# schematic_drive_2024-08-23.net
KiCad netlist of a schematic drawn in Altium Designer
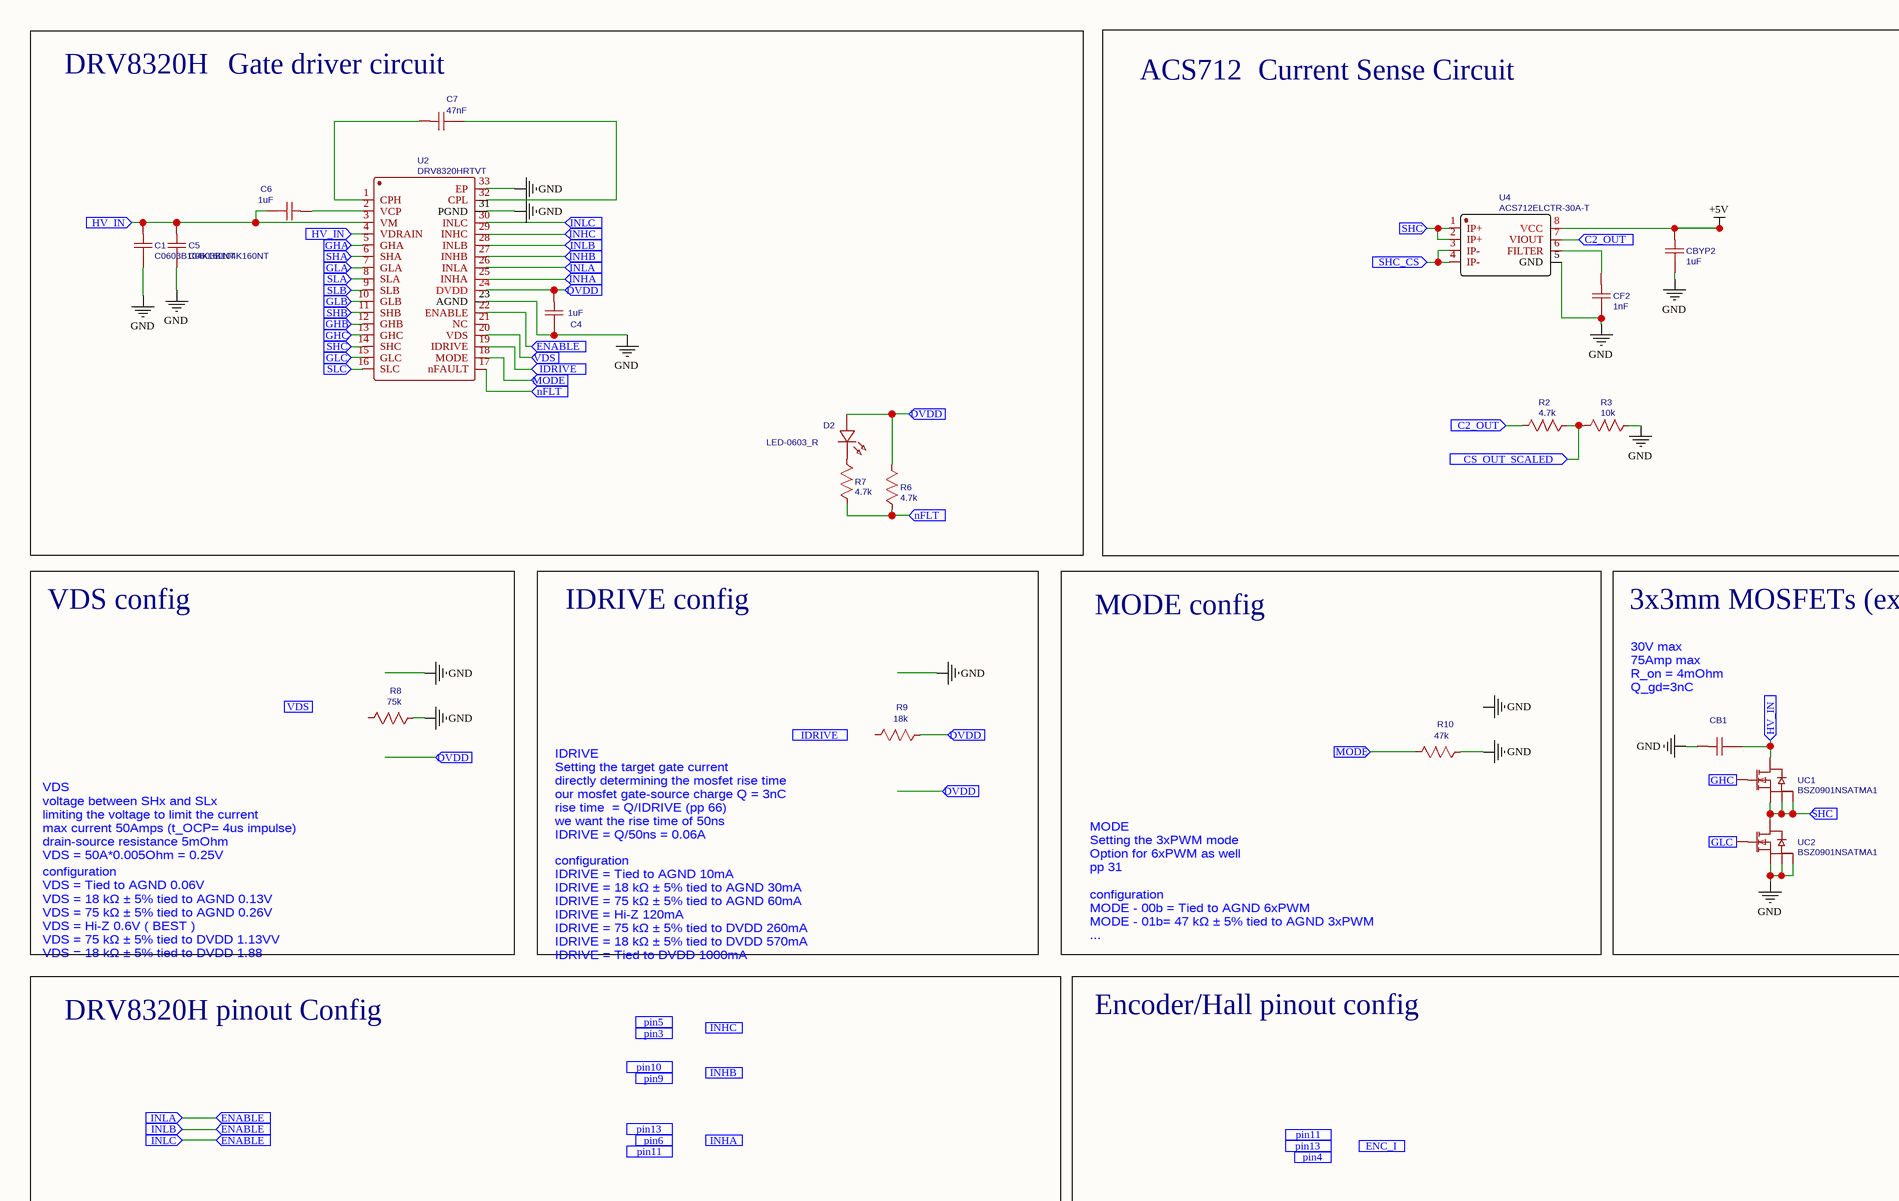
[diagram p0: schematic_drive_2024-08-23.schdoc, top left]
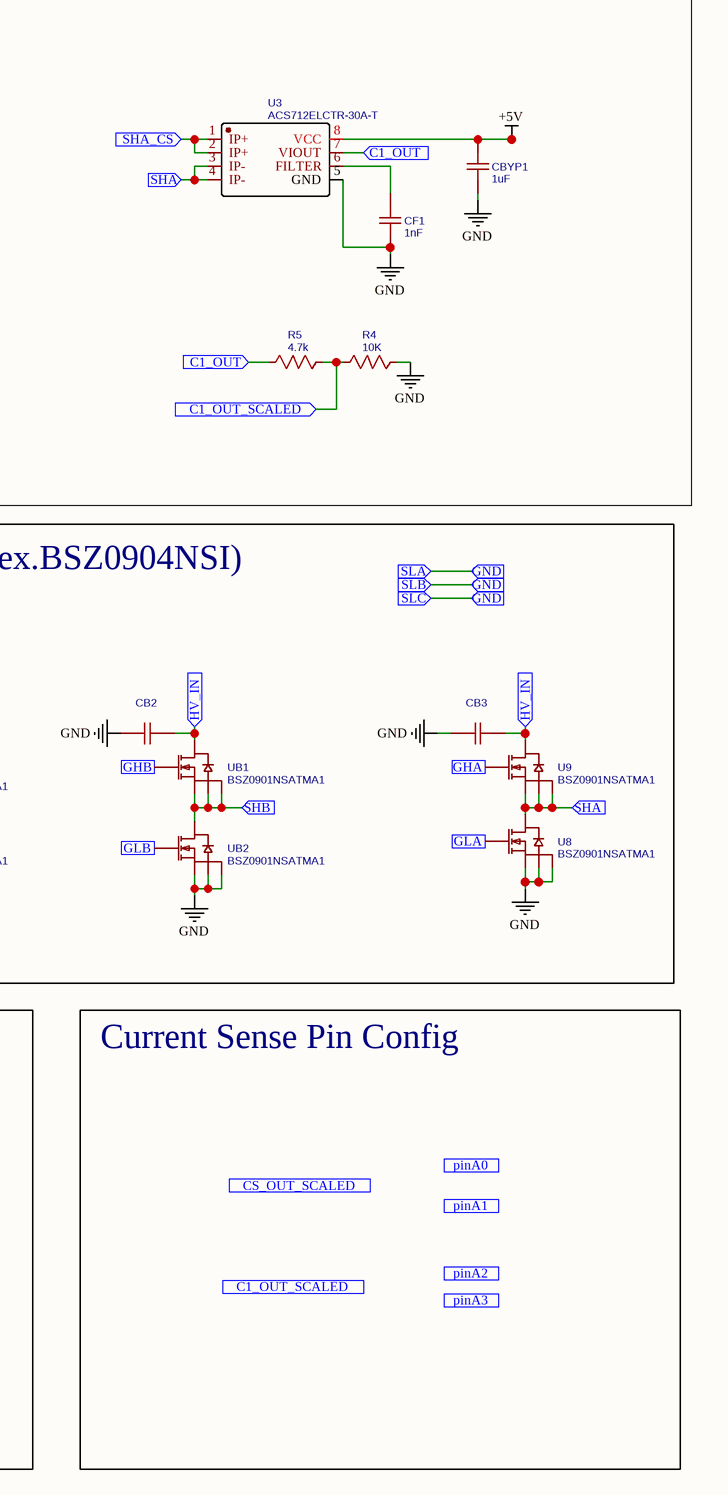
[diagram p1: schematic_drive_2024-08-23.schdoc, top right]
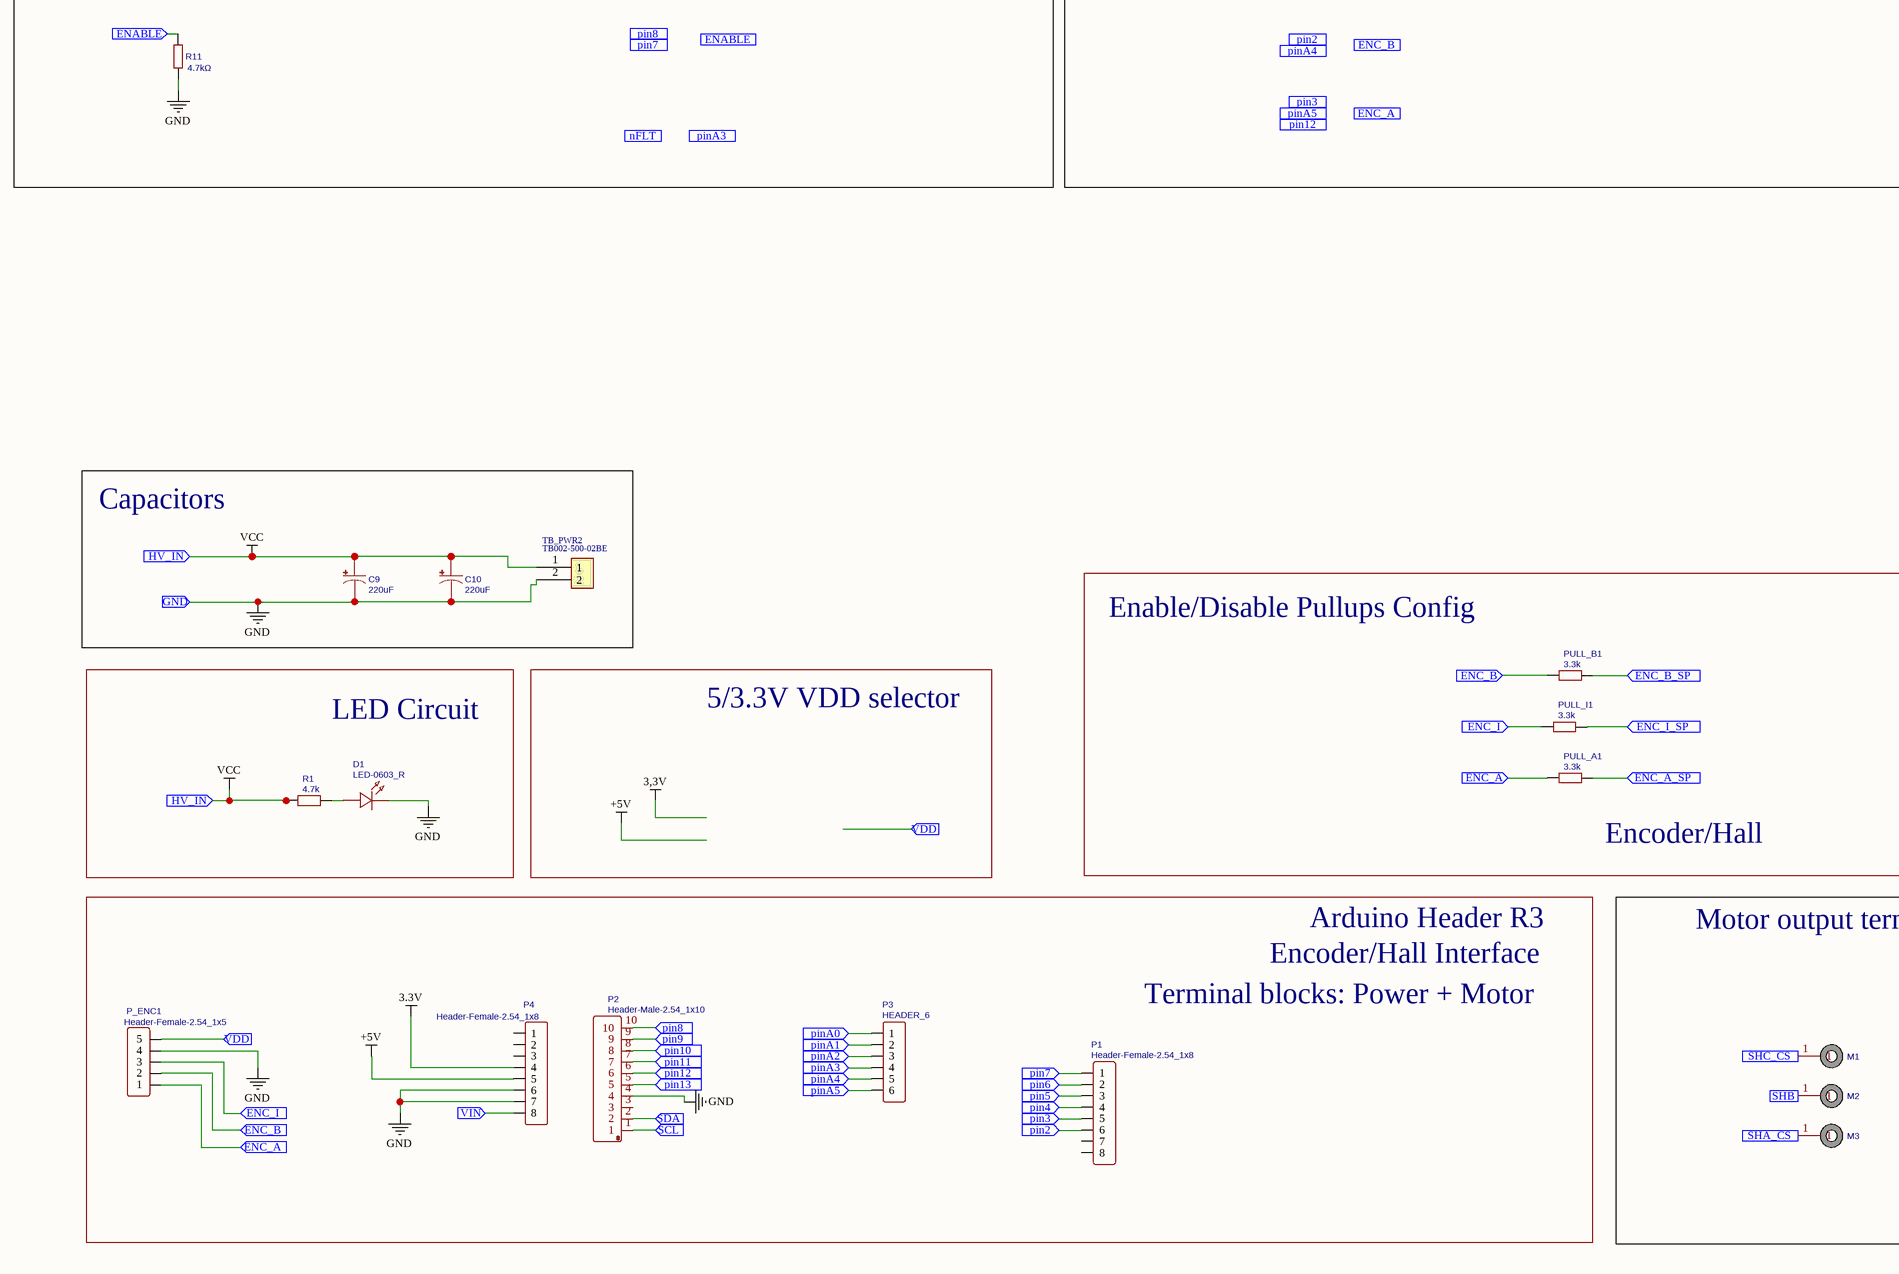
[diagram p2: schematic_drive_2024-08-23.schdoc, bottom left]
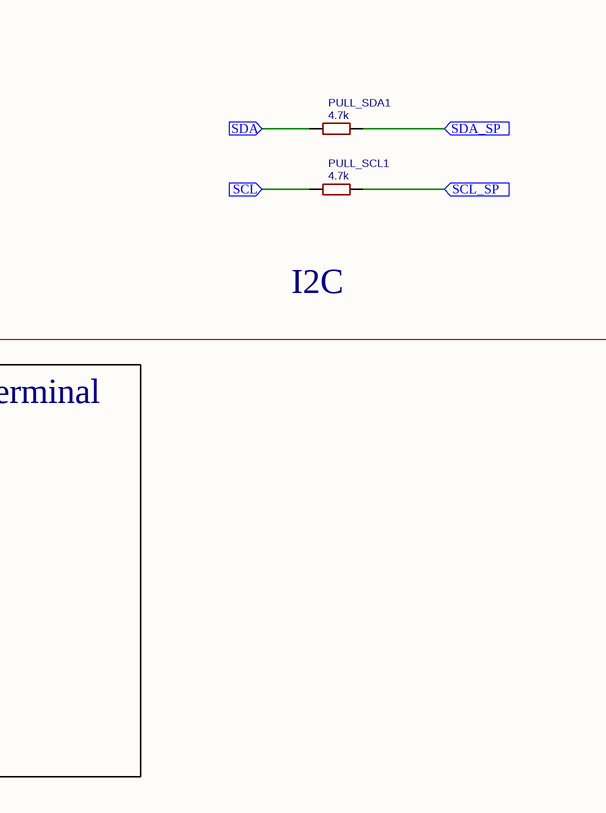
[diagram p3: schematic_drive_2024-08-23.schdoc, bottom right]

(export (version "E")
  (design (tool "Eeschema 10.0.6"))
  (components
    (comp (ref "C1")
      (value "C0603B104K160NT")
      (fields (field (name "MANUFACTURER") "TORCH(火炬)") (field (name "CONTRIBUTOR") "lcsc"))
      (libsource (lib "altium-import") (part "root_1_C0603B104K160NT_"))
    )
    (comp (ref "C4")
      (value "1uF")
      (fields (field (name "CONTRIBUTOR") "LCEDA_Lib"))
      (libsource (lib "altium-import") (part "root_1_1uF_"))
    )
    (comp (ref "C5")
      (value "C0603B104K160NT")
      (fields (field (name "MANUFACTURER") "TORCH(火炬)") (field (name "CONTRIBUTOR") "lcsc"))
      (libsource (lib "altium-import") (part "root_1_C0603B104K160NT_"))
    )
    (comp (ref "C6")
      (value "1uF")
      (fields (field (name "CONTRIBUTOR") "LCEDA_Lib"))
      (libsource (lib "altium-import") (part "root_0_1uF_"))
    )
    (comp (ref "C7")
      (value "47nF")
      (fields (field (name "CONTRIBUTOR") "LCEDA_Lib"))
      (libsource (lib "altium-import") (part "root_2_47nF_"))
    )
    (comp (ref "C9")
      (value "220uF")
      (fields
        (field (name "MANUFACTURER") "VT(首科)")
        (field (name "MANUFACTURER PART") "VT1V221M-CRF10")
        (field (name "CONTRIBUTOR") "LCSC")
      )
      (libsource (lib "altium-import") (part "root_0_220uF_"))
    )
    (comp (ref "C10")
      (value "220uF")
      (fields
        (field (name "MANUFACTURER") "VT(首科)")
        (field (name "MANUFACTURER PART") "VT1V221M-CRF10")
        (field (name "CONTRIBUTOR") "LCSC")
      )
      (libsource (lib "altium-import") (part "root_0_220uF_"))
    )
    (comp (ref "CB1")
      (value "C0603B104K160NT")
      (fields (field (name "MANUFACTURER") "TORCH(火炬)") (field (name "CONTRIBUTOR") "lcsc"))
      (libsource (lib "altium-import") (part "root_2_C0603B104K160NT_"))
    )
    (comp (ref "CB2")
      (value "C0603B104K160NT")
      (fields (field (name "MANUFACTURER") "TORCH(火炬)") (field (name "CONTRIBUTOR") "lcsc"))
      (libsource (lib "altium-import") (part "root_0_C0603B104K160NT_"))
    )
    (comp (ref "CB3")
      (value "C0603B104K160NT")
      (fields (field (name "MANUFACTURER") "TORCH(火炬)") (field (name "CONTRIBUTOR") "lcsc"))
      (libsource (lib "altium-import") (part "root_2_C0603B104K160NT_"))
    )
    (comp (ref "CBYP1")
      (value "1uF")
      (fields (field (name "CONTRIBUTOR") "LCEDA_Lib"))
      (libsource (lib "altium-import") (part "root_1_1uF_"))
    )
    (comp (ref "CBYP2")
      (value "1uF")
      (fields (field (name "CONTRIBUTOR") "LCEDA_Lib"))
      (libsource (lib "altium-import") (part "root_1_1uF_"))
    )
    (comp (ref "CF1")
      (value "1nF")
      (fields (field (name "CONTRIBUTOR") "LCEDA_Lib"))
      (libsource (lib "altium-import") (part "root_1_1nF_"))
    )
    (comp (ref "CF2")
      (value "1nF")
      (fields (field (name "CONTRIBUTOR") "LCEDA_Lib"))
      (libsource (lib "altium-import") (part "root_1_1nF_"))
    )
    (comp (ref "D1")
      (value "LED-0603_R")
      (fields
        (field (name "MANUFACTURER") "EVERLIGHT(台湾亿光)")
        (field (name "MANUFACTURER PART") "19-217/R6C-AL1M2VY/3T")
        (field (name "CONTRIBUTOR") "LCEDA_01")
      )
      (libsource (lib "altium-import") (part "root_0_LED-0603_R_"))
    )
    (comp (ref "D2")
      (value "LED-0603_R")
      (fields
        (field (name "MANUFACTURER") "EVERLIGHT(台湾亿光)")
        (field (name "MANUFACTURER PART") "19-217/R6C-AL1M2VY/3T")
        (field (name "CONTRIBUTOR") "LCEDA_01")
      )
      (libsource (lib "altium-import") (part "root_3_LED-0603_R_"))
    )
    (comp (ref "M1")
      (value "M2 PLATED HOLE WITH MINI HOLES")
      (fields (field (name "CONTRIBUTOR") "Andrew Young"))
      (libsource (lib "altium-import") (part "root_0_M2 PLATED HOLE WITH MINI HOLES_"))
    )
    (comp (ref "M2")
      (value "M2 PLATED HOLE WITH MINI HOLES")
      (fields (field (name "CONTRIBUTOR") "Andrew Young"))
      (libsource (lib "altium-import") (part "root_0_M2 PLATED HOLE WITH MINI HOLES_"))
    )
    (comp (ref "M3")
      (value "M2 PLATED HOLE WITH MINI HOLES")
      (fields (field (name "CONTRIBUTOR") "Andrew Young"))
      (libsource (lib "altium-import") (part "root_0_M2 PLATED HOLE WITH MINI HOLES_"))
    )
    (comp (ref "P1")
      (value "Header-Female-2.54_1x8")
      (fields
        (field (name "MANUFACTURER") "BOOMELE")
        (field (name "MANUFACTURER PART") "Female headerHDR1X8-2.54")
      )
      (libsource (lib "altium-import") (part "root_0_Header-Female-2.54_1x8_"))
    )
    (comp (ref "P2")
      (value "Header-Male-2.54_1x10")
      (fields (field (name "MANUFACTURER PART") "Headers  Pins2.54mm1*10P"))
      (libsource (lib "altium-import") (part "root_2_Header-Male-2.54_1x10_"))
    )
    (comp (ref "P3") (value "HEADER_6") (libsource (lib "altium-import") (part "root_0_HEADER_6_")))
    (comp (ref "P4")
      (value "Header-Female-2.54_1x8")
      (fields
        (field (name "MANUFACTURER") "BOOMELE")
        (field (name "MANUFACTURER PART") "Female headerHDR1X8-2.54")
      )
      (libsource (lib "altium-import") (part "root_0_Header-Female-2.54_1x8_"))
    )
    (comp (ref "PULL_A1") (value "3.3k") (libsource (lib "altium-import") (part "root_2_3.3k_")))
    (comp (ref "PULL_B1") (value "3.3k") (libsource (lib "altium-import") (part "root_2_3.3k_")))
    (comp (ref "PULL_I1") (value "3.3k") (libsource (lib "altium-import") (part "root_2_3.3k_")))
    (comp (ref "PULL_SCL1")
      (value "4.7k")
      (fields (field (name "MANUFACTURER") "UniOhm") (field (name "MANUFACTURER PART") "0603WAF4701T5E"))
      (libsource (lib "altium-import") (part "root_2_4.7k_"))
    )
    (comp (ref "PULL_SDA1")
      (value "4.7k")
      (fields (field (name "MANUFACTURER") "UniOhm") (field (name "MANUFACTURER PART") "0603WAF4701T5E"))
      (libsource (lib "altium-import") (part "root_2_4.7k_"))
    )
    (comp (ref "P_ENC1")
      (value "Header-Female-2.54_1x5")
      (fields
        (field (name "MANUFACTURER") "BOOMELE")
        (field (name "MANUFACTURER PART") "2.54mm 1*5p Female header")
      )
      (libsource (lib "altium-import") (part "root_2_Header-Female-2.54_1x5_"))
    )
    (comp (ref "R1")
      (value "4.7k")
      (fields (field (name "MANUFACTURER") "UniOhm") (field (name "MANUFACTURER PART") "0603WAF4701T5E"))
      (libsource (lib "altium-import") (part "root_2_4.7k_"))
    )
    (comp (ref "R2")
      (value "4.7k")
      (fields (field (name "CONTRIBUTOR") "LCEDA_Lib"))
      (libsource (lib "altium-import") (part "root_0_4.7k_"))
    )
    (comp (ref "R3")
      (value "10k")
      (fields (field (name "CONTRIBUTOR") "LCEDA_Lib"))
      (libsource (lib "altium-import") (part "root_0_10k_"))
    )
    (comp (ref "R4")
      (value "10K")
      (fields (field (name "CONTRIBUTOR") "LCEDA_Lib"))
      (libsource (lib "altium-import") (part "root_0_10K_"))
    )
    (comp (ref "R5")
      (value "4.7k")
      (fields (field (name "CONTRIBUTOR") "LCEDA_Lib"))
      (libsource (lib "altium-import") (part "root_0_4.7k_"))
    )
    (comp (ref "R6")
      (value "4.7k")
      (fields (field (name "CONTRIBUTOR") "LCEDA_Lib"))
      (libsource (lib "altium-import") (part "root_1_4.7k_"))
    )
    (comp (ref "R7")
      (value "4.7k")
      (fields (field (name "CONTRIBUTOR") "LCEDA_Lib"))
      (libsource (lib "altium-import") (part "root_1_4.7k_"))
    )
    (comp (ref "R8")
      (value "75k")
      (fields (field (name "CONTRIBUTOR") "LCEDA_Lib"))
      (libsource (lib "altium-import") (part "root_0_75k_"))
    )
    (comp (ref "R9")
      (value "18k")
      (fields (field (name "CONTRIBUTOR") "LCEDA_Lib"))
      (libsource (lib "altium-import") (part "root_0_18k_"))
    )
    (comp (ref "R10")
      (value "47k")
      (fields (field (name "CONTRIBUTOR") "LCEDA_Lib"))
      (libsource (lib "altium-import") (part "root_0_47k_"))
    )
    (comp (ref "R11")
      (value "4.7kΩ")
      (fields (field (name "MANUFACTURER") "UniOhm") (field (name "MANUFACTURER PART") "0603WAF4701T5E"))
      (libsource (lib "altium-import") (part "root_1_4.7kΩ_"))
    )
    (comp (ref "TB_PWR2")
      (value "TB002-500-02BE")
      (libsource (lib "altium-import") (part "root_2_TB002-500-02BE_"))
    )
    (comp (ref "U2")
      (value "DRV8320HRTVT")
      (fields (field (name "MANUFACTURER") "TI(德州仪器)") (field (name "CONTRIBUTOR") "LCSC"))
      (libsource (lib "altium-import") (part "root_0_DRV8320HRTVT_"))
    )
    (comp (ref "U3")
      (value "ACS712ELCTR-30A-T")
      (fields (field (name "MANUFACTURER") "ALLEGRO(美国埃戈罗)"))
      (libsource (lib "altium-import") (part "root_0_ACS712ELCTR-30A-T_"))
    )
    (comp (ref "U4")
      (value "ACS712ELCTR-30A-T")
      (fields (field (name "MANUFACTURER") "ALLEGRO(美国埃戈罗)"))
      (libsource (lib "altium-import") (part "root_0_ACS712ELCTR-30A-T_"))
    )
    (comp (ref "U8")
      (value "BSZ0901NSATMA1")
      (fields (field (name "MANUFACTURER") "Infineon(英飞凌)") (field (name "CONTRIBUTOR") "lcsc"))
      (libsource (lib "altium-import") (part "root_0_BSZ0901NSATMA1_"))
    )
    (comp (ref "U9")
      (value "BSZ0901NSATMA1")
      (fields (field (name "MANUFACTURER") "Infineon(英飞凌)") (field (name "CONTRIBUTOR") "lcsc"))
      (libsource (lib "altium-import") (part "root_0_BSZ0901NSATMA1_"))
    )
    (comp (ref "UB1")
      (value "BSZ0901NSATMA1")
      (fields (field (name "MANUFACTURER") "Infineon(英飞凌)") (field (name "CONTRIBUTOR") "lcsc"))
      (libsource (lib "altium-import") (part "root_0_BSZ0901NSATMA1_"))
    )
    (comp (ref "UB2")
      (value "BSZ0901NSATMA1")
      (fields (field (name "MANUFACTURER") "Infineon(英飞凌)") (field (name "CONTRIBUTOR") "lcsc"))
      (libsource (lib "altium-import") (part "root_0_BSZ0901NSATMA1_"))
    )
    (comp (ref "UC1")
      (value "BSZ0901NSATMA1")
      (fields (field (name "MANUFACTURER") "Infineon(英飞凌)") (field (name "CONTRIBUTOR") "lcsc"))
      (libsource (lib "altium-import") (part "root_0_BSZ0901NSATMA1_"))
    )
    (comp (ref "UC2")
      (value "BSZ0901NSATMA1")
      (fields (field (name "MANUFACTURER") "Infineon(英飞凌)") (field (name "CONTRIBUTOR") "lcsc"))
      (libsource (lib "altium-import") (part "root_0_BSZ0901NSATMA1_"))
    )
  )
  (nets
    (net (code "1") (name "+5V") (class "Default")
      (node (ref "CBYP1") (pin "2") (pinfunction "2_2") (pintype "passive"))
      (node (ref "CBYP2") (pin "2") (pinfunction "2_2") (pintype "passive"))
      (node (ref "P4") (pin "5") (pinfunction "5_5") (pintype "passive"))
      (node (ref "U3") (pin "8") (pinfunction "VCC_8") (pintype "passive"))
      (node (ref "U4") (pin "8") (pinfunction "VCC_8") (pintype "passive"))
    )
    (net (code "2") (name "/C1_OUT") (class "Default")
      (node (ref "R5") (pin "1") (pinfunction "1_1") (pintype "passive"))
      (node (ref "U3") (pin "7") (pinfunction "VIOUT_7") (pintype "passive"))
    )
    (net (code "3") (name "/C1_OUT_SCALED") (class "Default")
      (node (ref "R4") (pin "1") (pinfunction "1_1") (pintype "passive"))
      (node (ref "R5") (pin "2") (pinfunction "2_2") (pintype "passive"))
    )
    (net (code "4") (name "/C2_OUT") (class "Default")
      (node (ref "R2") (pin "1") (pinfunction "1_1") (pintype "passive"))
      (node (ref "U4") (pin "7") (pinfunction "VIOUT_7") (pintype "passive"))
    )
    (net (code "5") (name "/CS_OUT_SCALED") (class "Default")
      (node (ref "R2") (pin "2") (pinfunction "2_2") (pintype "passive"))
      (node (ref "R3") (pin "1") (pinfunction "1_1") (pintype "passive"))
    )
    (net (code "6") (name "/DVDD") (class "Default")
      (node (ref "C4") (pin "2") (pinfunction "2_2") (pintype "passive"))
      (node (ref "D2") (pin "1") (pinfunction "1_1") (pintype "passive"))
      (node (ref "R6") (pin "2") (pinfunction "2_2") (pintype "passive"))
      (node (ref "R9") (pin "2") (pinfunction "2_2") (pintype "passive"))
      (node (ref "U2") (pin "24") (pinfunction "DVDD_24") (pintype "passive"))
    )
    (net (code "7") (name "/ENABLE") (class "Default")
      (node (ref "R11") (pin "2") (pinfunction "2_2") (pintype "passive"))
      (node (ref "U2") (pin "22") (pinfunction "ENABLE_22") (pintype "passive"))
      (node (ref "U2") (pin "26") (pinfunction "INLA_26") (pintype "passive"))
      (node (ref "U2") (pin "28") (pinfunction "INLB_28") (pintype "passive"))
      (node (ref "U2") (pin "30") (pinfunction "INLC_30") (pintype "passive"))
    )
    (net (code "8") (name "/ENC_A") (class "Default")
      (node (ref "PULL_A1") (pin "2") (pinfunction "2_2") (pintype "passive"))
      (node (ref "P_ENC1") (pin "1") (pinfunction "1_1") (pintype "passive"))
    )
    (net (code "9") (name "/ENC_A_SP") (class "Default")
      (node (ref "PULL_A1") (pin "1") (pinfunction "1_1") (pintype "passive"))
    )
    (net (code "10") (name "/ENC_B") (class "Default")
      (node (ref "PULL_B1") (pin "2") (pinfunction "2_2") (pintype "passive"))
      (node (ref "P_ENC1") (pin "2") (pinfunction "2_2") (pintype "passive"))
    )
    (net (code "11") (name "/ENC_B_SP") (class "Default")
      (node (ref "PULL_B1") (pin "1") (pinfunction "1_1") (pintype "passive"))
    )
    (net (code "12") (name "/ENC_I") (class "Default")
      (node (ref "PULL_I1") (pin "2") (pinfunction "2_2") (pintype "passive"))
      (node (ref "P_ENC1") (pin "3") (pinfunction "3_3") (pintype "passive"))
    )
    (net (code "13") (name "/ENC_I_SP") (class "Default")
      (node (ref "PULL_I1") (pin "1") (pinfunction "1_1") (pintype "passive"))
    )
    (net (code "14") (name "/GHA") (class "Default")
      (node (ref "U2") (pin "5") (pinfunction "GHA_5") (pintype "passive"))
      (node (ref "U9") (pin "4") (pinfunction "G_4") (pintype "passive"))
    )
    (net (code "15") (name "/GHB") (class "Default")
      (node (ref "U2") (pin "12") (pinfunction "GHB_12") (pintype "passive"))
      (node (ref "UB1") (pin "4") (pinfunction "G_4") (pintype "passive"))
    )
    (net (code "16") (name "/GHC") (class "Default")
      (node (ref "U2") (pin "13") (pinfunction "GHC_13") (pintype "passive"))
      (node (ref "UC1") (pin "4") (pinfunction "G_4") (pintype "passive"))
    )
    (net (code "17") (name "/GLA") (class "Default")
      (node (ref "U2") (pin "7") (pinfunction "GLA_7") (pintype "passive"))
      (node (ref "U8") (pin "4") (pinfunction "G_4") (pintype "passive"))
    )
    (net (code "18") (name "/GLB") (class "Default")
      (node (ref "U2") (pin "10") (pinfunction "GLB_10") (pintype "passive"))
      (node (ref "UB2") (pin "4") (pinfunction "G_4") (pintype "passive"))
    )
    (net (code "19") (name "/GLC") (class "Default")
      (node (ref "U2") (pin "15") (pinfunction "GLC_15") (pintype "passive"))
      (node (ref "UC2") (pin "4") (pinfunction "G_4") (pintype "passive"))
    )
    (net (code "20") (name "/IDRIVE") (class "Default")
      (node (ref "U2") (pin "19") (pinfunction "IDRIVE_19") (pintype "passive"))
    )
    (net (code "21") (name "/INHA") (class "Default")
      (node (ref "U2") (pin "25") (pinfunction "INHA_25") (pintype "passive"))
    )
    (net (code "22") (name "/INHB") (class "Default")
      (node (ref "U2") (pin "27") (pinfunction "INHB_27") (pintype "passive"))
    )
    (net (code "23") (name "/INHC") (class "Default")
      (node (ref "U2") (pin "29") (pinfunction "INHC_29") (pintype "passive"))
    )
    (net (code "24") (name "/MODE") (class "Default")
      (node (ref "R10") (pin "1") (pinfunction "1_1") (pintype "passive"))
      (node (ref "U2") (pin "18") (pinfunction "MODE_18") (pintype "passive"))
    )
    (net (code "25") (name "/SCL") (class "Default")
      (node (ref "P2") (pin "1") (pinfunction "1_1") (pintype "passive"))
      (node (ref "PULL_SCL1") (pin "2") (pinfunction "2_2") (pintype "passive"))
    )
    (net (code "26") (name "/SCL_SP") (class "Default")
      (node (ref "PULL_SCL1") (pin "1") (pinfunction "1_1") (pintype "passive"))
    )
    (net (code "27") (name "/SDA") (class "Default")
      (node (ref "P2") (pin "2") (pinfunction "2_2") (pintype "passive"))
      (node (ref "PULL_SDA1") (pin "2") (pinfunction "2_2") (pintype "passive"))
    )
    (net (code "28") (name "/SDA_SP") (class "Default")
      (node (ref "PULL_SDA1") (pin "1") (pinfunction "1_1") (pintype "passive"))
    )
    (net (code "29") (name "/SHA") (class "Default")
      (node (ref "U2") (pin "6") (pinfunction "SHA_6") (pintype "passive"))
      (node (ref "U3") (pin "3") (pinfunction "IP-_3") (pintype "passive"))
      (node (ref "U3") (pin "4") (pinfunction "IP-_4") (pintype "passive"))
      (node (ref "U8") (pin "5") (pinfunction "D_5") (pintype "passive"))
      (node (ref "U9") (pin "1") (pinfunction "S_1") (pintype "passive"))
      (node (ref "U9") (pin "2") (pinfunction "S_2") (pintype "passive"))
      (node (ref "U9") (pin "3") (pinfunction "S_3") (pintype "passive"))
    )
    (net (code "30") (name "/SHA_CS") (class "Default")
      (node (ref "M3") (pin "1") (pinfunction "1_1") (pintype "passive"))
      (node (ref "U3") (pin "1") (pinfunction "IP+_1") (pintype "passive"))
      (node (ref "U3") (pin "2") (pinfunction "IP+_2") (pintype "passive"))
    )
    (net (code "31") (name "/SHB") (class "Default")
      (node (ref "M2") (pin "1") (pinfunction "1_1") (pintype "passive"))
      (node (ref "U2") (pin "11") (pinfunction "SHB_11") (pintype "passive"))
      (node (ref "UB1") (pin "1") (pinfunction "S_1") (pintype "passive"))
      (node (ref "UB1") (pin "2") (pinfunction "S_2") (pintype "passive"))
      (node (ref "UB1") (pin "3") (pinfunction "S_3") (pintype "passive"))
      (node (ref "UB2") (pin "5") (pinfunction "D_5") (pintype "passive"))
    )
    (net (code "32") (name "/SHC") (class "Default")
      (node (ref "U2") (pin "14") (pinfunction "SHC_14") (pintype "passive"))
      (node (ref "U4") (pin "1") (pinfunction "IP+_1") (pintype "passive"))
      (node (ref "U4") (pin "2") (pinfunction "IP+_2") (pintype "passive"))
      (node (ref "UC1") (pin "1") (pinfunction "S_1") (pintype "passive"))
      (node (ref "UC1") (pin "2") (pinfunction "S_2") (pintype "passive"))
      (node (ref "UC1") (pin "3") (pinfunction "S_3") (pintype "passive"))
      (node (ref "UC2") (pin "5") (pinfunction "D_5") (pintype "passive"))
    )
    (net (code "33") (name "/SHC_CS") (class "Default")
      (node (ref "M1") (pin "1") (pinfunction "1_1") (pintype "passive"))
      (node (ref "U4") (pin "3") (pinfunction "IP-_3") (pintype "passive"))
      (node (ref "U4") (pin "4") (pinfunction "IP-_4") (pintype "passive"))
    )
    (net (code "34") (name "/VDD") (class "Default")
      (node (ref "P_ENC1") (pin "5") (pinfunction "5_5") (pintype "passive"))
    )
    (net (code "35") (name "/VDS") (class "Default")
      (node (ref "U2") (pin "20") (pinfunction "VDS_20") (pintype "passive"))
    )
    (net (code "36") (name "/VIN") (class "Default")
      (node (ref "P4") (pin "8") (pinfunction "8_8") (pintype "passive"))
    )
    (net (code "37") (name "/nFLT") (class "Default")
      (node (ref "R6") (pin "1") (pinfunction "1_1") (pintype "passive"))
      (node (ref "R7") (pin "1") (pinfunction "1_1") (pintype "passive"))
      (node (ref "U2") (pin "17") (pinfunction "nFAULT_17") (pintype "passive"))
    )
    (net (code "38") (name "/pin2") (class "Default")
      (node (ref "P1") (pin "6") (pinfunction "6_6") (pintype "passive"))
    )
    (net (code "39") (name "/pin3") (class "Default")
      (node (ref "P1") (pin "5") (pinfunction "5_5") (pintype "passive"))
    )
    (net (code "40") (name "/pin4") (class "Default")
      (node (ref "P1") (pin "4") (pinfunction "4_4") (pintype "passive"))
    )
    (net (code "41") (name "/pin5") (class "Default")
      (node (ref "P1") (pin "3") (pinfunction "3_3") (pintype "passive"))
    )
    (net (code "42") (name "/pin6") (class "Default")
      (node (ref "P1") (pin "2") (pinfunction "2_2") (pintype "passive"))
    )
    (net (code "43") (name "/pin7") (class "Default")
      (node (ref "P1") (pin "1") (pinfunction "1_1") (pintype "passive"))
    )
    (net (code "44") (name "/pin8") (class "Default")
      (node (ref "P2") (pin "10") (pinfunction "10_10") (pintype "passive"))
    )
    (net (code "45") (name "/pin9") (class "Default")
      (node (ref "P2") (pin "9") (pinfunction "9_9") (pintype "passive"))
    )
    (net (code "46") (name "/pin10") (class "Default")
      (node (ref "P2") (pin "8") (pinfunction "8_8") (pintype "passive"))
    )
    (net (code "47") (name "/pin11") (class "Default")
      (node (ref "P2") (pin "7") (pinfunction "7_7") (pintype "passive"))
    )
    (net (code "48") (name "/pin12") (class "Default")
      (node (ref "P2") (pin "6") (pinfunction "6_6") (pintype "passive"))
    )
    (net (code "49") (name "/pin13") (class "Default")
      (node (ref "P2") (pin "5") (pinfunction "5_5") (pintype "passive"))
    )
    (net (code "50") (name "/pinA0") (class "Default")
      (node (ref "P3") (pin "1") (pinfunction "1_1") (pintype "passive"))
    )
    (net (code "51") (name "/pinA1") (class "Default")
      (node (ref "P3") (pin "2") (pinfunction "2_2") (pintype "passive"))
    )
    (net (code "52") (name "/pinA2") (class "Default")
      (node (ref "P3") (pin "3") (pinfunction "3_3") (pintype "passive"))
    )
    (net (code "53") (name "/pinA3") (class "Default")
      (node (ref "P3") (pin "4") (pinfunction "4_4") (pintype "passive"))
    )
    (net (code "54") (name "/pinA4") (class "Default")
      (node (ref "P3") (pin "5") (pinfunction "5_5") (pintype "passive"))
    )
    (net (code "55") (name "/pinA5") (class "Default")
      (node (ref "P3") (pin "6") (pinfunction "6_6") (pintype "passive"))
    )
    (net (code "57") (name "3.3V") (class "Default")
      (node (ref "P4") (pin "4") (pinfunction "4_4") (pintype "passive"))
    )
    (net (code "58") (name "GND") (class "Default")
      (node (ref "C1") (pin "1") (pinfunction "1_1") (pintype "passive"))
      (node (ref "C10") (pin "2") (pinfunction "2_2") (pintype "passive"))
      (node (ref "C4") (pin "1") (pinfunction "1_1") (pintype "passive"))
      (node (ref "C5") (pin "1") (pinfunction "1_1") (pintype "passive"))
      (node (ref "C9") (pin "2") (pinfunction "2_2") (pintype "passive"))
      (node (ref "CB1") (pin "2") (pinfunction "2_2") (pintype "passive"))
      (node (ref "CB2") (pin "1") (pinfunction "1_1") (pintype "passive"))
      (node (ref "CB3") (pin "2") (pinfunction "2_2") (pintype "passive"))
      (node (ref "CBYP1") (pin "1") (pinfunction "1_1") (pintype "passive"))
      (node (ref "CBYP2") (pin "1") (pinfunction "1_1") (pintype "passive"))
      (node (ref "CF1") (pin "1") (pinfunction "1_1") (pintype "passive"))
      (node (ref "CF2") (pin "1") (pinfunction "1_1") (pintype "passive"))
      (node (ref "D1") (pin "2") (pinfunction "2_2") (pintype "passive"))
      (node (ref "P2") (pin "4") (pinfunction "4_4") (pintype "passive"))
      (node (ref "P4") (pin "6") (pinfunction "6_6") (pintype "passive"))
      (node (ref "P4") (pin "7") (pinfunction "7_7") (pintype "passive"))
      (node (ref "P_ENC1") (pin "4") (pinfunction "4_4") (pintype "passive"))
      (node (ref "R10") (pin "2") (pinfunction "2_2") (pintype "passive"))
      (node (ref "R11") (pin "1") (pinfunction "1_1") (pintype "passive"))
      (node (ref "R3") (pin "2") (pinfunction "2_2") (pintype "passive"))
      (node (ref "R4") (pin "2") (pinfunction "2_2") (pintype "passive"))
      (node (ref "R8") (pin "2") (pinfunction "2_2") (pintype "passive"))
      (node (ref "TB_PWR2") (pin "2") (pinfunction "2_2") (pintype "passive"))
      (node (ref "U2") (pin "16") (pinfunction "SLC_16") (pintype "passive"))
      (node (ref "U2") (pin "23") (pinfunction "AGND_23") (pintype "passive"))
      (node (ref "U2") (pin "31") (pinfunction "PGND_31") (pintype "passive"))
      (node (ref "U2") (pin "33") (pinfunction "EP_33") (pintype "passive"))
      (node (ref "U2") (pin "8") (pinfunction "SLA_8") (pintype "passive"))
      (node (ref "U2") (pin "9") (pinfunction "SLB_9") (pintype "passive"))
      (node (ref "U3") (pin "5") (pinfunction "GND_5") (pintype "passive"))
      (node (ref "U4") (pin "5") (pinfunction "GND_5") (pintype "passive"))
      (node (ref "U8") (pin "1") (pinfunction "S_1") (pintype "passive"))
      (node (ref "U8") (pin "2") (pinfunction "S_2") (pintype "passive"))
      (node (ref "U8") (pin "3") (pinfunction "S_3") (pintype "passive"))
      (node (ref "UB2") (pin "1") (pinfunction "S_1") (pintype "passive"))
      (node (ref "UB2") (pin "2") (pinfunction "S_2") (pintype "passive"))
      (node (ref "UB2") (pin "3") (pinfunction "S_3") (pintype "passive"))
      (node (ref "UC2") (pin "1") (pinfunction "S_1") (pintype "passive"))
      (node (ref "UC2") (pin "2") (pinfunction "S_2") (pintype "passive"))
      (node (ref "UC2") (pin "3") (pinfunction "S_3") (pintype "passive"))
    )
    (net (code "59") (name "Net-(D1-Pad1)") (class "Default")
      (node (ref "D1") (pin "1") (pinfunction "1_1") (pintype "passive"))
      (node (ref "R1") (pin "1") (pinfunction "1_1") (pintype "passive"))
    )
    (net (code "60") (name "Net-(D2-Pad2)") (class "Default")
      (node (ref "D2") (pin "2") (pinfunction "2_2") (pintype "passive"))
      (node (ref "R7") (pin "2") (pinfunction "2_2") (pintype "passive"))
    )
    (net (code "61") (name "Net-(U2-CPH)") (class "Default")
      (node (ref "C7") (pin "2") (pinfunction "2_2") (pintype "passive"))
      (node (ref "U2") (pin "1") (pinfunction "CPH_1") (pintype "passive"))
    )
    (net (code "62") (name "Net-(U2-CPL)") (class "Default")
      (node (ref "C7") (pin "1") (pinfunction "1_1") (pintype "passive"))
      (node (ref "U2") (pin "32") (pinfunction "CPL_32") (pintype "passive"))
    )
    (net (code "63") (name "Net-(U2-VCP)") (class "Default")
      (node (ref "C6") (pin "2") (pinfunction "2_2") (pintype "passive"))
      (node (ref "U2") (pin "2") (pinfunction "VCP_2") (pintype "passive"))
    )
    (net (code "64") (name "Net-(U3-FILTER)") (class "Default")
      (node (ref "CF1") (pin "2") (pinfunction "2_2") (pintype "passive"))
      (node (ref "U3") (pin "6") (pinfunction "FILTER_6") (pintype "passive"))
    )
    (net (code "65") (name "Net-(U4-FILTER)") (class "Default")
      (node (ref "CF2") (pin "2") (pinfunction "2_2") (pintype "passive"))
      (node (ref "U4") (pin "6") (pinfunction "FILTER_6") (pintype "passive"))
    )
    (net (code "66") (name "VCC") (class "Default")
      (node (ref "C1") (pin "2") (pinfunction "2_2") (pintype "passive"))
      (node (ref "C10") (pin "1") (pinfunction "1_1") (pintype "passive"))
      (node (ref "C5") (pin "2") (pinfunction "2_2") (pintype "passive"))
      (node (ref "C6") (pin "1") (pinfunction "1_1") (pintype "passive"))
      (node (ref "C9") (pin "1") (pinfunction "1_1") (pintype "passive"))
      (node (ref "CB1") (pin "1") (pinfunction "1_1") (pintype "passive"))
      (node (ref "CB2") (pin "2") (pinfunction "2_2") (pintype "passive"))
      (node (ref "CB3") (pin "1") (pinfunction "1_1") (pintype "passive"))
      (node (ref "R1") (pin "2") (pinfunction "2_2") (pintype "passive"))
      (node (ref "TB_PWR2") (pin "1") (pinfunction "1_1") (pintype "passive"))
      (node (ref "U2") (pin "3") (pinfunction "VM_3") (pintype "passive"))
      (node (ref "U2") (pin "4") (pinfunction "VDRAIN_4") (pintype "passive"))
      (node (ref "U9") (pin "5") (pinfunction "D_5") (pintype "passive"))
      (node (ref "UB1") (pin "5") (pinfunction "D_5") (pintype "passive"))
      (node (ref "UC1") (pin "5") (pinfunction "D_5") (pintype "passive"))
    )
    (net (code "67") (name "unconnected-(P1-Pad7)") (class "Default")
      (node (ref "P1") (pin "7") (pinfunction "7_7") (pintype "passive"))
    )
    (net (code "68") (name "unconnected-(P1-Pad8)") (class "Default")
      (node (ref "P1") (pin "8") (pinfunction "8_8") (pintype "passive"))
    )
    (net (code "69") (name "unconnected-(P2-Pad3)") (class "Default")
      (node (ref "P2") (pin "3") (pinfunction "3_3") (pintype "passive"))
    )
    (net (code "70") (name "unconnected-(P4-Pad1)") (class "Default")
      (node (ref "P4") (pin "1") (pinfunction "1_1") (pintype "passive"))
    )
    (net (code "71") (name "unconnected-(P4-Pad2)") (class "Default")
      (node (ref "P4") (pin "2") (pinfunction "2_2") (pintype "passive"))
    )
    (net (code "72") (name "unconnected-(P4-Pad3)") (class "Default")
      (node (ref "P4") (pin "3") (pinfunction "3_3") (pintype "passive"))
    )
    (net (code "73") (name "unconnected-(R8-Pad1)") (class "Default")
      (node (ref "R8") (pin "1") (pinfunction "1_1") (pintype "passive"))
    )
    (net (code "74") (name "unconnected-(R9-Pad1)") (class "Default")
      (node (ref "R9") (pin "1") (pinfunction "1_1") (pintype "passive"))
    )
    (net (code "75") (name "unconnected-(U2-NC-Pad21)") (class "Default")
      (node (ref "U2") (pin "21") (pinfunction "NC_21") (pintype "passive"))
    )
  )
)
